# PWR_SRC.net
KiCad netlist of a schematic drawn in Altium Designer
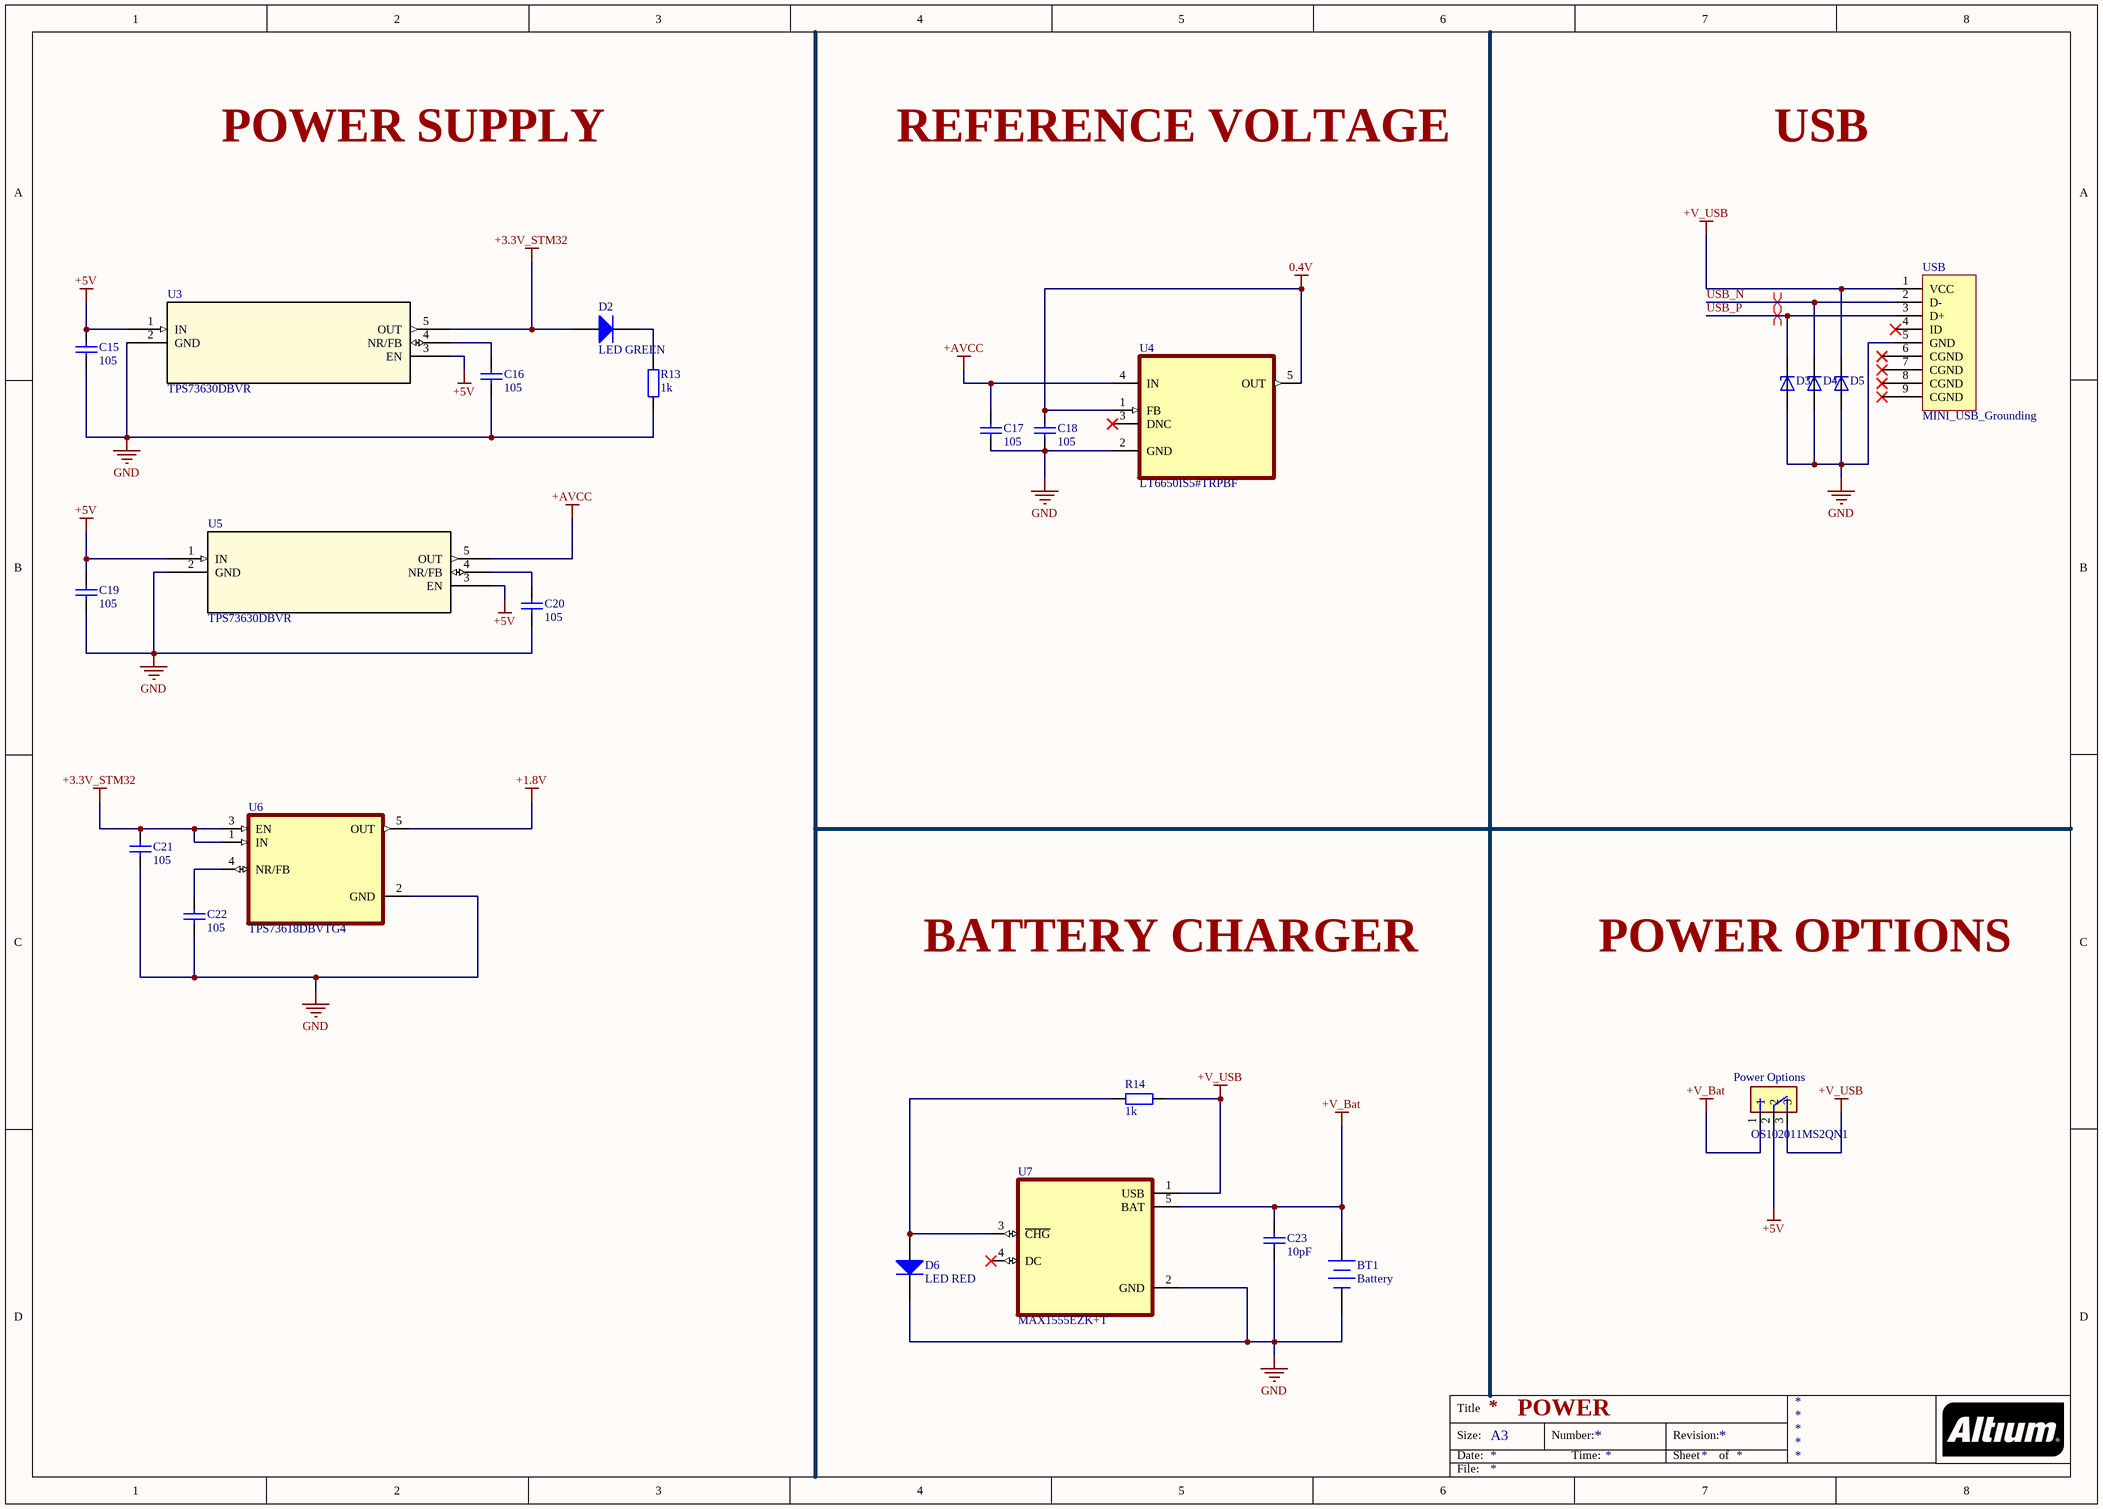
[diagram p0: PWR_SRC.SchDoc]

(export (version "E")
  (design (tool "Eeschema 10.0.6"))
  (components
    (comp (ref "BT1")
      (value "Battery")
      (footprint "BAT-2")
      (description "Multicell Battery")
      (fields (field (name "PUBLISHER") "Altium Limited"))
      (libsource (lib "Miscellaneous Devices") (part "Battery"))
    )
    (comp (ref "C15")
      (value "105")
      (footprint "tu 0603")
      (description "Dán")
      (libsource (lib "Altium_Lib_by_KhueNguyenCreator") (part "Tu 0603 105 16V 20%"))
    )
    (comp (ref "C16")
      (value "105")
      (footprint "tu 0603")
      (description "Dán")
      (libsource (lib "Altium_Lib_by_KhueNguyenCreator") (part "Tu 0603 105 16V 20%"))
    )
    (comp (ref "C17")
      (value "105")
      (footprint "tu 0603")
      (description "Dán")
      (libsource (lib "Altium_Lib_by_KhueNguyenCreator") (part "Tu 0603 105 16V 20%"))
    )
    (comp (ref "C18")
      (value "105")
      (footprint "tu 0603")
      (description "Dán")
      (libsource (lib "Altium_Lib_by_KhueNguyenCreator") (part "Tu 0603 105 16V 20%"))
    )
    (comp (ref "C19")
      (value "105")
      (footprint "tu 0603")
      (description "Dán")
      (libsource (lib "Altium_Lib_by_KhueNguyenCreator") (part "Tu 0603 105 16V 20%"))
    )
    (comp (ref "C20")
      (value "105")
      (footprint "tu 0603")
      (description "Dán")
      (libsource (lib "Altium_Lib_by_KhueNguyenCreator") (part "Tu 0603 105 16V 20%"))
    )
    (comp (ref "C21")
      (value "105")
      (footprint "tu 0603")
      (description "Dán")
      (libsource (lib "Altium_Lib_by_KhueNguyenCreator") (part "Tu 0603 105 16V 20%"))
    )
    (comp (ref "C22")
      (value "105")
      (footprint "tu 0603")
      (description "Dán")
      (libsource (lib "Altium_Lib_by_KhueNguyenCreator") (part "Tu 0603 105 16V 20%"))
    )
    (comp (ref "C23")
      (value "10pF")
      (footprint "tu 0805")
      (description "Dán")
      (libsource (lib "Altium_Lib_by_KhueNguyenCreator") (part "Tu 0805 10pF 50V 10%"))
    )
    (comp (ref "D2")
      (value "LED GREEN")
      (footprint "J1-0603")
      (description "Default Diode")
      (fields (field (name "PUBLISHER") "Altium Limited"))
      (libsource (lib "MSP430_sch_1060821") (part "Diode"))
    )
    (comp (ref "D3")
      (value "AVRL161A1R1NTA")
      (footprint "AVRL161A1R1NTA:TVS_AVRL161A1R1NTA")
      (fields (field (name "MF") "{'manufacturer': u'TDK'}"))
      (libsource (lib "*") (part "AVRL161A1R1NTA"))
    )
    (comp (ref "D4")
      (value "AVRL161A1R1NTA")
      (footprint "AVRL161A1R1NTA:TVS_AVRL161A1R1NTA")
      (fields (field (name "MF") "{'manufacturer': u'TDK'}"))
      (libsource (lib "*") (part "AVRL161A1R1NTA"))
    )
    (comp (ref "D5")
      (value "AVRL161A1R1NTA")
      (footprint "AVRL161A1R1NTA:TVS_AVRL161A1R1NTA")
      (fields (field (name "MF") "{'manufacturer': u'TDK'}"))
      (libsource (lib "*") (part "AVRL161A1R1NTA"))
    )
    (comp (ref "D6")
      (value "LED RED")
      (footprint "J1-0603")
      (description "Default Diode")
      (fields (field (name "PUBLISHER") "Altium Limited"))
      (libsource (lib "MSP430_sch_1060821") (part "Diode"))
    )
    (comp (ref "Power Options")
      (value "OS102011MS2QN1")
      (footprint "SW_OS102011MS2QN1")
      (description "Switch Slide ON ON SPDT Top Slide 0.1A 12VDC 10000Cycles PC Pins Thru-Hole Bulk")
      (fields (field (name "MF") "{'manufacturer': u'C&K'}"))
      (libsource (lib "SnapEDA_Library") (part "OS102011MS2QN1"))
    )
    (comp (ref "R13")
      (value "1k")
      (footprint "tro smd 0603")
      (description "Dán")
      (libsource (lib "Altium_Lib_by_KhueNguyenCreator") (part "Tro 0603 5% 1k"))
    )
    (comp (ref "R14")
      (value "1k")
      (footprint "tro smd 0603")
      (description "Dán")
      (libsource (lib "Altium_Lib_by_KhueNguyenCreator") (part "Tro 0603 1% 1k"))
    )
    (comp (ref "U3")
      (value "TPS73630DBVR")
      (footprint "DBV5-M")
      (description "No Description Available")
      (libsource (lib "TPS73630DBVR") (part "TPS73630DBVR"))
    )
    (comp (ref "U4")
      (value "LT6650IS5#TRPBF")
      (footprint "SOT95P280X100-5N")
      (description "Micropower, 400mV Reference with Rail-to-Rail Buffer Amplifier")
      (fields (field (name "MF") "{'manufacturer': u'Analog Devices'}"))
      (libsource (lib "SnapEDA_Library") (part "LT6650IS5#TRPBF"))
    )
    (comp (ref "U5")
      (value "TPS73630DBVR")
      (footprint "DBV5-M")
      (description "No Description Available")
      (libsource (lib "TPS73630DBVR") (part "TPS73630DBVR"))
    )
    (comp (ref "U6")
      (value "TPS73618DBVTG4")
      (footprint "TPS73618DBVTG4:SOT95P280X145-5N")
      (fields (field (name "MF") "{'manufacturer': u'Texas Instruments'}"))
      (libsource (lib "*") (part "TPS73618DBVTG4"))
    )
    (comp (ref "U7")
      (value "MAX1555EZK+T")
      (footprint "SOT95P275X110-5N")
      (fields (field (name "MF") "{'manufacturer': u'Analog Devices'}") (field (name "MP") "MAX1555EZK+"))
      (libsource (lib "SnapEDA_Library") (part "MAX1555EZK+T"))
    )
    (comp (ref "USB")
      (value "MINI_USB_Grounding")
      (footprint "micro_USB shilding")
      (libsource (lib "MSP430_sch_1061121") (part "MINI_USB_Grounding"))
    )
  )
  (nets
    (net (code "1") (name "+1.8V") (class "Default")
      (node (ref "U6") (pin "5") (pinfunction "OUT_5") (pintype "output"))
    )
    (net (code "2") (name "+3.3V_STM32") (class "Default")
      (node (ref "C21") (pin "1") (pinfunction "1_1") (pintype "passive"))
      (node (ref "D2") (pin "1") (pinfunction "A_1") (pintype "passive"))
      (node (ref "U3") (pin "5") (pinfunction "OUT_5") (pintype "output"))
      (node (ref "U6") (pin "1") (pinfunction "IN_1") (pintype "input"))
      (node (ref "U6") (pin "3") (pinfunction "EN_3") (pintype "input"))
    )
    (net (code "3") (name "+5V") (class "Default")
      (node (ref "C15") (pin "1") (pinfunction "1_1") (pintype "passive"))
      (node (ref "C19") (pin "1") (pinfunction "1_1") (pintype "passive"))
      (node (ref "Power Options") (pin "2") (pinfunction "2_2") (pintype "passive"))
      (node (ref "U3") (pin "1") (pinfunction "IN_1") (pintype "input"))
      (node (ref "U3") (pin "3") (pinfunction "EN_3") (pintype "passive"))
      (node (ref "U5") (pin "1") (pinfunction "IN_1") (pintype "input"))
      (node (ref "U5") (pin "3") (pinfunction "EN_3") (pintype "passive"))
    )
    (net (code "4") (name "+AVCC") (class "Default")
      (node (ref "C17") (pin "1") (pinfunction "1_1") (pintype "passive"))
      (node (ref "U4") (pin "4") (pinfunction "IN_4") (pintype "power_in"))
      (node (ref "U5") (pin "5") (pinfunction "OUT_5") (pintype "output"))
    )
    (net (code "5") (name "+V_Bat") (class "Default")
      (node (ref "BT1") (pin "1") (pinfunction "+_1") (pintype "passive"))
      (node (ref "C23") (pin "1") (pinfunction "1_1") (pintype "passive"))
      (node (ref "Power Options") (pin "1") (pinfunction "1_1") (pintype "passive"))
      (node (ref "U7") (pin "5") (pinfunction "BAT_5") (pintype "power_in"))
    )
    (net (code "6") (name "+V_USB") (class "Default")
      (node (ref "D5") (pin "1") (pinfunction "C_1") (pintype "passive"))
      (node (ref "Power Options") (pin "3") (pinfunction "3_3") (pintype "passive"))
      (node (ref "R14") (pin "2") (pinfunction "2_2") (pintype "passive"))
      (node (ref "U7") (pin "1") (pinfunction "USB_1") (pintype "power_in"))
      (node (ref "USB") (pin "1") (pinfunction "VCC_1") (pintype "passive"))
    )
    (net (code "7") (name "/USB_N") (class "Default")
      (node (ref "D4") (pin "1") (pinfunction "C_1") (pintype "passive"))
      (node (ref "USB") (pin "2") (pinfunction "D-_2") (pintype "passive"))
    )
    (net (code "8") (name "/USB_P") (class "Default")
      (node (ref "D3") (pin "1") (pinfunction "C_1") (pintype "passive"))
      (node (ref "USB") (pin "3") (pinfunction "D+_3") (pintype "passive"))
    )
    (net (code "9") (name "0.4V") (class "Default")
      (node (ref "C18") (pin "1") (pinfunction "1_1") (pintype "passive"))
      (node (ref "U4") (pin "1") (pinfunction "FB_1") (pintype "input"))
      (node (ref "U4") (pin "5") (pinfunction "OUT_5") (pintype "output"))
    )
    (net (code "10") (name "GND") (class "Default")
      (node (ref "BT1") (pin "2") (pinfunction "-_2") (pintype "passive"))
      (node (ref "C15") (pin "2") (pinfunction "2_2") (pintype "passive"))
      (node (ref "C16") (pin "2") (pinfunction "2_2") (pintype "passive"))
      (node (ref "C17") (pin "2") (pinfunction "2_2") (pintype "passive"))
      (node (ref "C18") (pin "2") (pinfunction "2_2") (pintype "passive"))
      (node (ref "C19") (pin "2") (pinfunction "2_2") (pintype "passive"))
      (node (ref "C20") (pin "2") (pinfunction "2_2") (pintype "passive"))
      (node (ref "C21") (pin "2") (pinfunction "2_2") (pintype "passive"))
      (node (ref "C22") (pin "2") (pinfunction "2_2") (pintype "passive"))
      (node (ref "C23") (pin "2") (pinfunction "2_2") (pintype "passive"))
      (node (ref "D3") (pin "2") (pinfunction "A_2") (pintype "passive"))
      (node (ref "D4") (pin "2") (pinfunction "A_2") (pintype "passive"))
      (node (ref "D5") (pin "2") (pinfunction "A_2") (pintype "passive"))
      (node (ref "D6") (pin "2") (pinfunction "K_2") (pintype "passive"))
      (node (ref "R13") (pin "2") (pinfunction "2_2") (pintype "passive"))
      (node (ref "U3") (pin "2") (pinfunction "GND_2") (pintype "power_in"))
      (node (ref "U4") (pin "2") (pinfunction "GND_2") (pintype "passive"))
      (node (ref "U5") (pin "2") (pinfunction "GND_2") (pintype "power_in"))
      (node (ref "U6") (pin "2") (pinfunction "GND_2") (pintype "power_in"))
      (node (ref "U7") (pin "2") (pinfunction "GND_2") (pintype "power_in"))
      (node (ref "USB") (pin "5") (pinfunction "GND_5") (pintype "passive"))
    )
    (net (code "11") (name "Net-(D2-K)") (class "Default")
      (node (ref "D2") (pin "2") (pinfunction "K_2") (pintype "passive"))
      (node (ref "R13") (pin "1") (pinfunction "1_1") (pintype "passive"))
    )
    (net (code "12") (name "Net-(D6-A)") (class "Default")
      (node (ref "D6") (pin "1") (pinfunction "A_1") (pintype "passive"))
      (node (ref "R14") (pin "1") (pinfunction "1_1") (pintype "passive"))
      (node (ref "U7") (pin "3") (pinfunction "~{CHG}_3") (pintype "bidirectional"))
    )
    (net (code "13") (name "Net-(U3-NR{slash}FB)") (class "Default")
      (node (ref "C16") (pin "1") (pinfunction "1_1") (pintype "passive"))
      (node (ref "U3") (pin "4") (pinfunction "NR/FB_4") (pintype "bidirectional"))
    )
    (net (code "14") (name "Net-(U5-NR{slash}FB)") (class "Default")
      (node (ref "C20") (pin "1") (pinfunction "1_1") (pintype "passive"))
      (node (ref "U5") (pin "4") (pinfunction "NR/FB_4") (pintype "bidirectional"))
    )
    (net (code "15") (name "Net-(U6-NR{slash}FB)") (class "Default")
      (node (ref "C22") (pin "1") (pinfunction "1_1") (pintype "passive"))
      (node (ref "U6") (pin "4") (pinfunction "NR/FB_4") (pintype "bidirectional"))
    )
    (net (code "16") (name "unconnected-(U4-DNC-Pad3)") (class "Default")
      (node (ref "U4") (pin "3") (pinfunction "DNC_3") (pintype "passive+no_connect"))
    )
    (net (code "17") (name "unconnected-(U7-DC-Pad4)") (class "Default")
      (node (ref "U7") (pin "4") (pinfunction "DC_4") (pintype "bidirectional+no_connect"))
    )
    (net (code "18") (name "unconnected-(USB-CGND-Pad6)") (class "Default")
      (node (ref "USB") (pin "6") (pinfunction "CGND_6") (pintype "passive+no_connect"))
    )
    (net (code "19") (name "unconnected-(USB-CGND-Pad7)") (class "Default")
      (node (ref "USB") (pin "7") (pinfunction "CGND_7") (pintype "passive+no_connect"))
    )
    (net (code "20") (name "unconnected-(USB-CGND-Pad8)") (class "Default")
      (node (ref "USB") (pin "8") (pinfunction "CGND_8") (pintype "passive+no_connect"))
    )
    (net (code "21") (name "unconnected-(USB-CGND-Pad9)") (class "Default")
      (node (ref "USB") (pin "9") (pinfunction "CGND_9") (pintype "passive+no_connect"))
    )
    (net (code "22") (name "unconnected-(USB-ID-Pad4)") (class "Default")
      (node (ref "USB") (pin "4") (pinfunction "ID_4") (pintype "passive+no_connect"))
    )
  )
)
